# Environmental_Module_-_Board.net
KiCad netlist of a schematic drawn in EAGLE
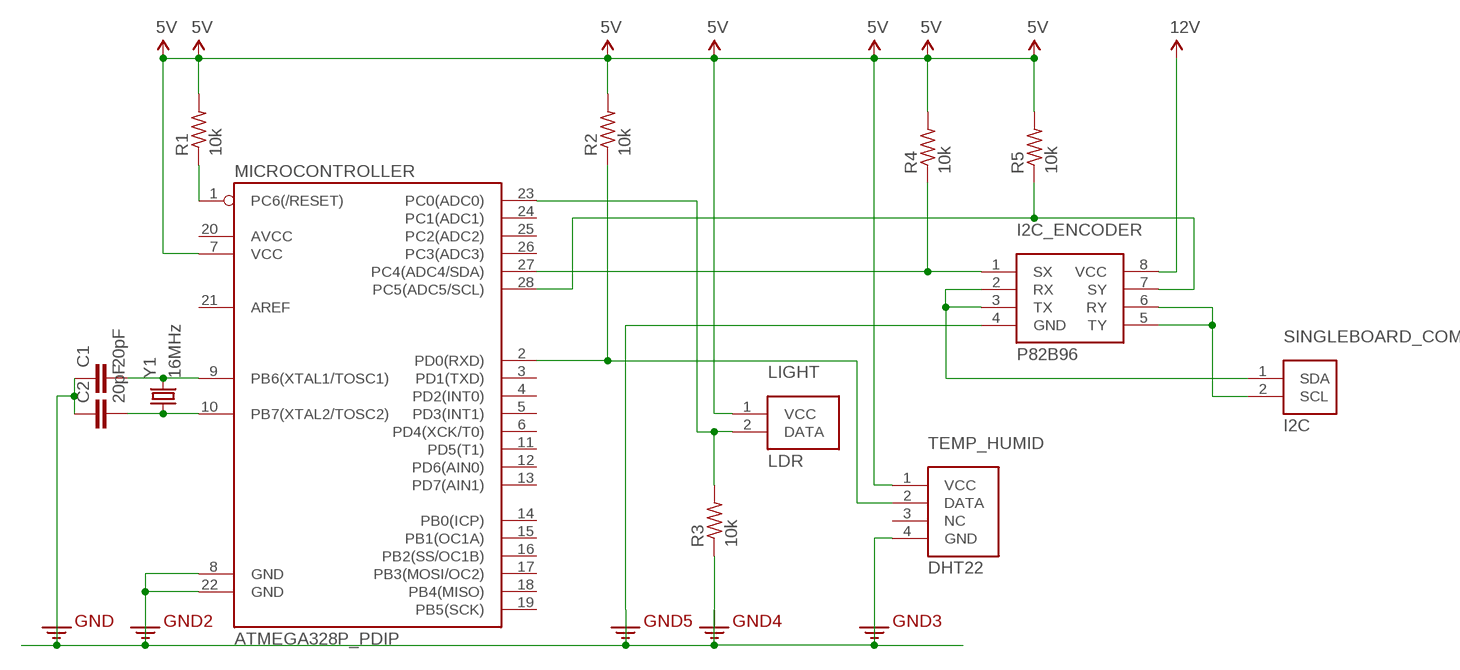
[diagram p0: schematic, sheet 1]

(export (version "E")
  (design (tool "Eeschema 10.0.6"))
  (components
    (comp (ref "C1")
      (value "20pF")
      (footprint "eagle-import:CAP-PTH-SMALL")
      (libsource (lib "eagle-import") (part "CAPPTH"))
    )
    (comp (ref "C2")
      (value "20pF")
      (footprint "eagle-import:CAP-PTH-SMALL")
      (libsource (lib "eagle-import") (part "CAPPTH"))
    )
    (comp (ref "I2C_ENCODER")
      (value "P82B96")
      (footprint "eagle-import:SOIC8")
      (libsource (lib "eagle-import") (part "P82B96"))
    )
    (comp (ref "LIGHT")
      (value "LDR")
      (footprint "eagle-import:LDR")
      (libsource (lib "eagle-import") (part "LDR"))
    )
    (comp (ref "MICROCONTROLLER")
      (value "ATMEGA328P_PDIP")
      (footprint "eagle-import:DIL28-3")
      (libsource (lib "eagle-import") (part "ATMEGA328P_PDIP"))
    )
    (comp (ref "R1")
      (value "10k")
      (footprint "eagle-import:0204_7")
      (libsource (lib "eagle-import") (part "R-US_0204/7"))
    )
    (comp (ref "R2")
      (value "10k")
      (footprint "eagle-import:0204_7")
      (libsource (lib "eagle-import") (part "R-US_0204/7"))
    )
    (comp (ref "R3")
      (value "10k")
      (footprint "eagle-import:0204_7")
      (libsource (lib "eagle-import") (part "R-US_0204/7"))
    )
    (comp (ref "R4")
      (value "10k")
      (footprint "eagle-import:0204_7")
      (libsource (lib "eagle-import") (part "R-US_0204/7"))
    )
    (comp (ref "R5")
      (value "10k")
      (footprint "eagle-import:0204_7")
      (libsource (lib "eagle-import") (part "R-US_0204/7"))
    )
    (comp (ref "SINGLEBOARD_COMP")
      (value "I2C")
      (footprint "eagle-import:LDR")
      (libsource (lib "eagle-import") (part "I2C"))
    )
    (comp (ref "TEMP_HUMID")
      (value "DHT22")
      (footprint "eagle-import:DHT22")
      (libsource (lib "eagle-import") (part "DHT22"))
    )
    (comp (ref "Y1")
      (value "16MHz")
      (footprint "eagle-import:HC49US")
      (libsource (lib "eagle-import") (part "CRYSTALHC49US"))
    )
  )
  (nets
    (net (code "1") (name "5V") (class "Default")
      (node (ref "LIGHT") (pin "1") (pinfunction "VCC_1") (pintype "bidirectional"))
      (node (ref "MICROCONTROLLER") (pin "7") (pinfunction "VCC_7") (pintype "bidirectional"))
      (node (ref "R1") (pin "2") (pinfunction "2_2") (pintype "passive"))
      (node (ref "R2") (pin "2") (pinfunction "2_2") (pintype "passive"))
      (node (ref "R4") (pin "2") (pinfunction "2_2") (pintype "passive"))
      (node (ref "R5") (pin "2") (pinfunction "2_2") (pintype "passive"))
      (node (ref "TEMP_HUMID") (pin "1") (pinfunction "VCC_1") (pintype "bidirectional"))
    )
    (net (code "2") (name "12V") (class "Default")
      (node (ref "I2C_ENCODER") (pin "8") (pinfunction "VCC_8") (pintype "bidirectional"))
    )
    (net (code "3") (name "GND2") (class "Default")
      (node (ref "C1") (pin "1") (pinfunction "1_1") (pintype "passive"))
      (node (ref "C2") (pin "1") (pinfunction "1_1") (pintype "passive"))
      (node (ref "I2C_ENCODER") (pin "4") (pinfunction "GND_4") (pintype "bidirectional"))
      (node (ref "MICROCONTROLLER") (pin "22") (pinfunction "GND_22") (pintype "bidirectional"))
      (node (ref "MICROCONTROLLER") (pin "8") (pinfunction "GND_8") (pintype "bidirectional"))
      (node (ref "R3") (pin "1") (pinfunction "1_1") (pintype "passive"))
      (node (ref "TEMP_HUMID") (pin "4") (pinfunction "GND_4") (pintype "bidirectional"))
    )
    (net (code "4") (name "Net-(I2C_ENCODER-RX)") (class "Default")
      (node (ref "I2C_ENCODER") (pin "2") (pinfunction "RX_2") (pintype "bidirectional"))
      (node (ref "I2C_ENCODER") (pin "3") (pinfunction "TX_3") (pintype "bidirectional"))
      (node (ref "SINGLEBOARD_COMP") (pin "1") (pinfunction "SDA_1") (pintype "bidirectional"))
    )
    (net (code "5") (name "Net-(I2C_ENCODER-RY)") (class "Default")
      (node (ref "I2C_ENCODER") (pin "5") (pinfunction "TY_5") (pintype "bidirectional"))
      (node (ref "I2C_ENCODER") (pin "6") (pinfunction "RY_6") (pintype "bidirectional"))
      (node (ref "SINGLEBOARD_COMP") (pin "2") (pinfunction "SCL_2") (pintype "bidirectional"))
    )
    (net (code "6") (name "Net-(I2C_ENCODER-SX)") (class "Default")
      (node (ref "I2C_ENCODER") (pin "1") (pinfunction "SX_1") (pintype "bidirectional"))
      (node (ref "MICROCONTROLLER") (pin "27") (pinfunction "PC4(ADC4/SDA)_27") (pintype "bidirectional"))
      (node (ref "R4") (pin "1") (pinfunction "1_1") (pintype "passive"))
    )
    (net (code "7") (name "Net-(I2C_ENCODER-SY)") (class "Default")
      (node (ref "I2C_ENCODER") (pin "7") (pinfunction "SY_7") (pintype "bidirectional"))
      (node (ref "MICROCONTROLLER") (pin "28") (pinfunction "PC5(ADC5/SCL)_28") (pintype "bidirectional"))
      (node (ref "R5") (pin "1") (pinfunction "1_1") (pintype "passive"))
    )
    (net (code "8") (name "Net-(LIGHT-DATA)") (class "Default")
      (node (ref "LIGHT") (pin "2") (pinfunction "DATA_2") (pintype "bidirectional"))
      (node (ref "MICROCONTROLLER") (pin "23") (pinfunction "PC0(ADC0)_23") (pintype "bidirectional"))
      (node (ref "R3") (pin "2") (pinfunction "2_2") (pintype "passive"))
    )
    (net (code "9") (name "Net-(MICROCONTROLLER-PB6(XTAL1{slash}TOSC1))") (class "Default")
      (node (ref "C1") (pin "2") (pinfunction "2_2") (pintype "passive"))
      (node (ref "MICROCONTROLLER") (pin "9") (pinfunction "PB6(XTAL1/TOSC1)_9") (pintype "bidirectional"))
      (node (ref "Y1") (pin "2") (pinfunction "2_2") (pintype "passive"))
    )
    (net (code "10") (name "Net-(MICROCONTROLLER-PB7(XTAL2{slash}TOSC2))") (class "Default")
      (node (ref "C2") (pin "2") (pinfunction "2_2") (pintype "passive"))
      (node (ref "MICROCONTROLLER") (pin "10") (pinfunction "PB7(XTAL2/TOSC2)_10") (pintype "bidirectional"))
      (node (ref "Y1") (pin "1") (pinfunction "1_1") (pintype "passive"))
    )
    (net (code "11") (name "Net-(MICROCONTROLLER-PC6({slash}RESET))") (class "Default")
      (node (ref "MICROCONTROLLER") (pin "1") (pinfunction "PC6(/RESET)_1") (pintype "bidirectional"))
      (node (ref "R1") (pin "1") (pinfunction "1_1") (pintype "passive"))
    )
    (net (code "12") (name "Net-(MICROCONTROLLER-PD0(RXD))") (class "Default")
      (node (ref "MICROCONTROLLER") (pin "2") (pinfunction "PD0(RXD)_2") (pintype "bidirectional"))
      (node (ref "R2") (pin "1") (pinfunction "1_1") (pintype "passive"))
      (node (ref "TEMP_HUMID") (pin "2") (pinfunction "DATA_2") (pintype "bidirectional"))
    )
    (net (code "13") (name "unconnected-(MICROCONTROLLER-AREF-Pad21)") (class "Default")
      (node (ref "MICROCONTROLLER") (pin "21") (pinfunction "AREF_21") (pintype "bidirectional"))
    )
    (net (code "14") (name "unconnected-(MICROCONTROLLER-AVCC-Pad20)") (class "Default")
      (node (ref "MICROCONTROLLER") (pin "20") (pinfunction "AVCC_20") (pintype "bidirectional"))
    )
    (net (code "15") (name "unconnected-(MICROCONTROLLER-PB0(ICP)-Pad14)") (class "Default")
      (node (ref "MICROCONTROLLER") (pin "14") (pinfunction "PB0(ICP)_14") (pintype "bidirectional"))
    )
    (net (code "16") (name "unconnected-(MICROCONTROLLER-PB1(OC1A)-Pad15)") (class "Default")
      (node (ref "MICROCONTROLLER") (pin "15") (pinfunction "PB1(OC1A)_15") (pintype "bidirectional"))
    )
    (net (code "17") (name "unconnected-(MICROCONTROLLER-PB2(SS{slash}OC1B)-Pad16)") (class "Default")
      (node (ref "MICROCONTROLLER") (pin "16") (pinfunction "PB2(SS/OC1B)_16") (pintype "bidirectional"))
    )
    (net (code "18") (name "unconnected-(MICROCONTROLLER-PB3(MOSI{slash}OC2)-Pad17)") (class "Default")
      (node (ref "MICROCONTROLLER") (pin "17") (pinfunction "PB3(MOSI/OC2)_17") (pintype "bidirectional"))
    )
    (net (code "19") (name "unconnected-(MICROCONTROLLER-PB4(MISO)-Pad18)") (class "Default")
      (node (ref "MICROCONTROLLER") (pin "18") (pinfunction "PB4(MISO)_18") (pintype "bidirectional"))
    )
    (net (code "20") (name "unconnected-(MICROCONTROLLER-PB5(SCK)-Pad19)") (class "Default")
      (node (ref "MICROCONTROLLER") (pin "19") (pinfunction "PB5(SCK)_19") (pintype "bidirectional"))
    )
    (net (code "21") (name "unconnected-(MICROCONTROLLER-PC1(ADC1)-Pad24)") (class "Default")
      (node (ref "MICROCONTROLLER") (pin "24") (pinfunction "PC1(ADC1)_24") (pintype "bidirectional"))
    )
    (net (code "22") (name "unconnected-(MICROCONTROLLER-PC2(ADC2)-Pad25)") (class "Default")
      (node (ref "MICROCONTROLLER") (pin "25") (pinfunction "PC2(ADC2)_25") (pintype "bidirectional"))
    )
    (net (code "23") (name "unconnected-(MICROCONTROLLER-PC3(ADC3)-Pad26)") (class "Default")
      (node (ref "MICROCONTROLLER") (pin "26") (pinfunction "PC3(ADC3)_26") (pintype "bidirectional"))
    )
    (net (code "24") (name "unconnected-(MICROCONTROLLER-PD1(TXD)-Pad3)") (class "Default")
      (node (ref "MICROCONTROLLER") (pin "3") (pinfunction "PD1(TXD)_3") (pintype "bidirectional"))
    )
    (net (code "25") (name "unconnected-(MICROCONTROLLER-PD2(INT0)-Pad4)") (class "Default")
      (node (ref "MICROCONTROLLER") (pin "4") (pinfunction "PD2(INT0)_4") (pintype "bidirectional"))
    )
    (net (code "26") (name "unconnected-(MICROCONTROLLER-PD3(INT1)-Pad5)") (class "Default")
      (node (ref "MICROCONTROLLER") (pin "5") (pinfunction "PD3(INT1)_5") (pintype "bidirectional"))
    )
    (net (code "27") (name "unconnected-(MICROCONTROLLER-PD4(XCK{slash}T0)-Pad6)") (class "Default")
      (node (ref "MICROCONTROLLER") (pin "6") (pinfunction "PD4(XCK/T0)_6") (pintype "bidirectional"))
    )
    (net (code "28") (name "unconnected-(MICROCONTROLLER-PD5(T1)-Pad11)") (class "Default")
      (node (ref "MICROCONTROLLER") (pin "11") (pinfunction "PD5(T1)_11") (pintype "bidirectional"))
    )
    (net (code "29") (name "unconnected-(MICROCONTROLLER-PD6(AIN0)-Pad12)") (class "Default")
      (node (ref "MICROCONTROLLER") (pin "12") (pinfunction "PD6(AIN0)_12") (pintype "bidirectional"))
    )
    (net (code "30") (name "unconnected-(MICROCONTROLLER-PD7(AIN1)-Pad13)") (class "Default")
      (node (ref "MICROCONTROLLER") (pin "13") (pinfunction "PD7(AIN1)_13") (pintype "bidirectional"))
    )
    (net (code "31") (name "unconnected-(TEMP_HUMID-NC-Pad3)") (class "Default")
      (node (ref "TEMP_HUMID") (pin "3") (pinfunction "NC_3") (pintype "bidirectional"))
    )
  )
)
